# CAN.net
KiCad netlist of a schematic drawn in Altium Designer
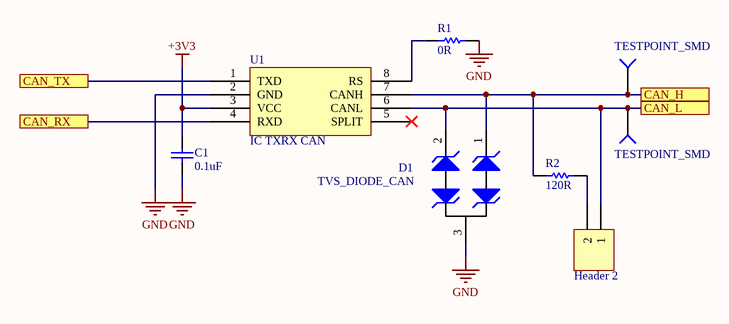
[diagram p0: CAN.SchDoc]

(export (version "E")
  (design (tool "Eeschema 10.0.6"))
  (components
    (comp (ref "1")
      (value "Header 2")
      (footprint "HDR1X2")
      (description "Header, 2-Pin")
      (fields (field (name "PUBLISHER") "Altium Limited"))
      (libsource (lib "Miscellaneous Connectors") (part "Header 2"))
    )
    (comp (ref "C1")
      (value "0.1uF")
      (footprint "CAPC0603(1608)55_N")
      (description "CAP CER 0.1UF 16V X7R 0603")
      (fields (field (name "PART NUMBER") "CC0603KRX7R7BB104") (field (name "MANUFACTURER") "Yageo"))
      (libsource (lib "UWRT_Schematic_Library_2019") (part "CAP_0.1uF_16V_0603"))
    )
    (comp (ref "D1")
      (value "TVS_DIODE_CAN")
      (footprint "UWRT_Footprint_Library_2019:TVS_DIODE_CAN")
      (description "TVS DIODE 24V 41V SOT323-3")
      (fields (field (name "PART NUMBER") "PESD2CAN,215") (field (name "MANUFACTURER") "Nexperia USA Inc."))
      (libsource (lib "UWRT_Schematic_Library_2019") (part "TVS_DIODE_CAN"))
    )
    (comp (ref "R1")
      (value "0R")
      (footprint "RESC0603(1608)_N")
      (description "RES SMD 0 OHM JUMPER 1/10W 0603")
      (fields (field (name "MANUFACTURER") "Yageo") (field (name "Comment") "RES_0R_0603"))
      (libsource (lib "UWRT_Schematic_Library_2019") (part "RES_0R_0603"))
    )
    (comp (ref "R2")
      (value "120R")
      (footprint "RESC0603(1608)_N")
      (description "RES SMD 120 OHM 5% 1/10W 0603")
      (fields (field (name "MANUFACTURER") "Yageo") (field (name "TOLERANCE") "5%"))
      (libsource (lib "UWRT_Schematic_Library_2019") (part "RES_120R_0603"))
    )
    (comp (ref "TP1")
      (value "TESTPOINT_SMD")
      (footprint "TESTPOINT")
      (libsource (lib "UWRT_Schematic_Library_2019") (part "TESTPOINT_SMD"))
    )
    (comp (ref "TP2")
      (value "TESTPOINT_SMD")
      (footprint "TESTPOINT")
      (libsource (lib "UWRT_Schematic_Library_2019") (part "TESTPOINT_SMD"))
    )
    (comp (ref "U1")
      (value "IC TXRX CAN")
      (footprint "LTC2875")
      (description "IC TXRX CAN 4MBPS 8SO")
      (fields
        (field (name "MANUFACTURER") "Linear Technologies")
        (field (name "PART NUMBER") "LTC2875IS8#PBF")
      )
      (libsource (lib "UWRT_Schematic_Library_2019") (part "LTC2875"))
    )
  )
  (nets
    (net (code "1") (name "+3V3") (class "Default")
      (node (ref "C1") (pin "2") (pinfunction "2_2") (pintype "passive"))
      (node (ref "U1") (pin "3") (pinfunction "VCC_3") (pintype "passive"))
    )
    (net (code "2") (name "/CAN_H") (class "Default")
      (node (ref "D1") (pin "1") (pinfunction "1_1") (pintype "passive"))
      (node (ref "R2") (pin "1") (pinfunction "1_1") (pintype "passive"))
      (node (ref "TP1") (pin "1") (pinfunction "=value_1") (pintype "passive"))
      (node (ref "U1") (pin "7") (pinfunction "CANH_7") (pintype "passive"))
    )
    (net (code "3") (name "/CAN_L") (class "Default")
      (node (ref "1") (pin "1") (pinfunction "1_1") (pintype "passive"))
      (node (ref "D1") (pin "2") (pinfunction "2_2") (pintype "passive"))
      (node (ref "TP2") (pin "1") (pinfunction "=value_1") (pintype "passive"))
      (node (ref "U1") (pin "6") (pinfunction "CANL_6") (pintype "passive"))
    )
    (net (code "4") (name "/CAN_RX") (class "Default")
      (node (ref "U1") (pin "4") (pinfunction "RXD_4") (pintype "passive"))
    )
    (net (code "5") (name "/CAN_TX") (class "Default")
      (node (ref "U1") (pin "1") (pinfunction "TXD_1") (pintype "passive"))
    )
    (net (code "6") (name "GND") (class "Default")
      (node (ref "C1") (pin "1") (pinfunction "1_1") (pintype "passive"))
      (node (ref "D1") (pin "3") (pinfunction "3_3") (pintype "passive"))
      (node (ref "R1") (pin "2") (pinfunction "2_2") (pintype "passive"))
      (node (ref "U1") (pin "2") (pinfunction "GND_2") (pintype "passive"))
    )
    (net (code "7") (name "Net-(1-Pad2)") (class "Default")
      (node (ref "1") (pin "2") (pinfunction "2_2") (pintype "passive"))
      (node (ref "R2") (pin "2") (pinfunction "2_2") (pintype "passive"))
    )
    (net (code "8") (name "Net-(U1-RS)") (class "Default")
      (node (ref "R1") (pin "1") (pinfunction "1_1") (pintype "passive"))
      (node (ref "U1") (pin "8") (pinfunction "RS_8") (pintype "passive"))
    )
    (net (code "9") (name "unconnected-(U1-SPLIT-Pad5)") (class "Default")
      (node (ref "U1") (pin "5") (pinfunction "SPLIT_5") (pintype "passive+no_connect"))
    )
  )
)
